# Battery_and_Charging.net
KiCad netlist of a schematic drawn in Altium Designer
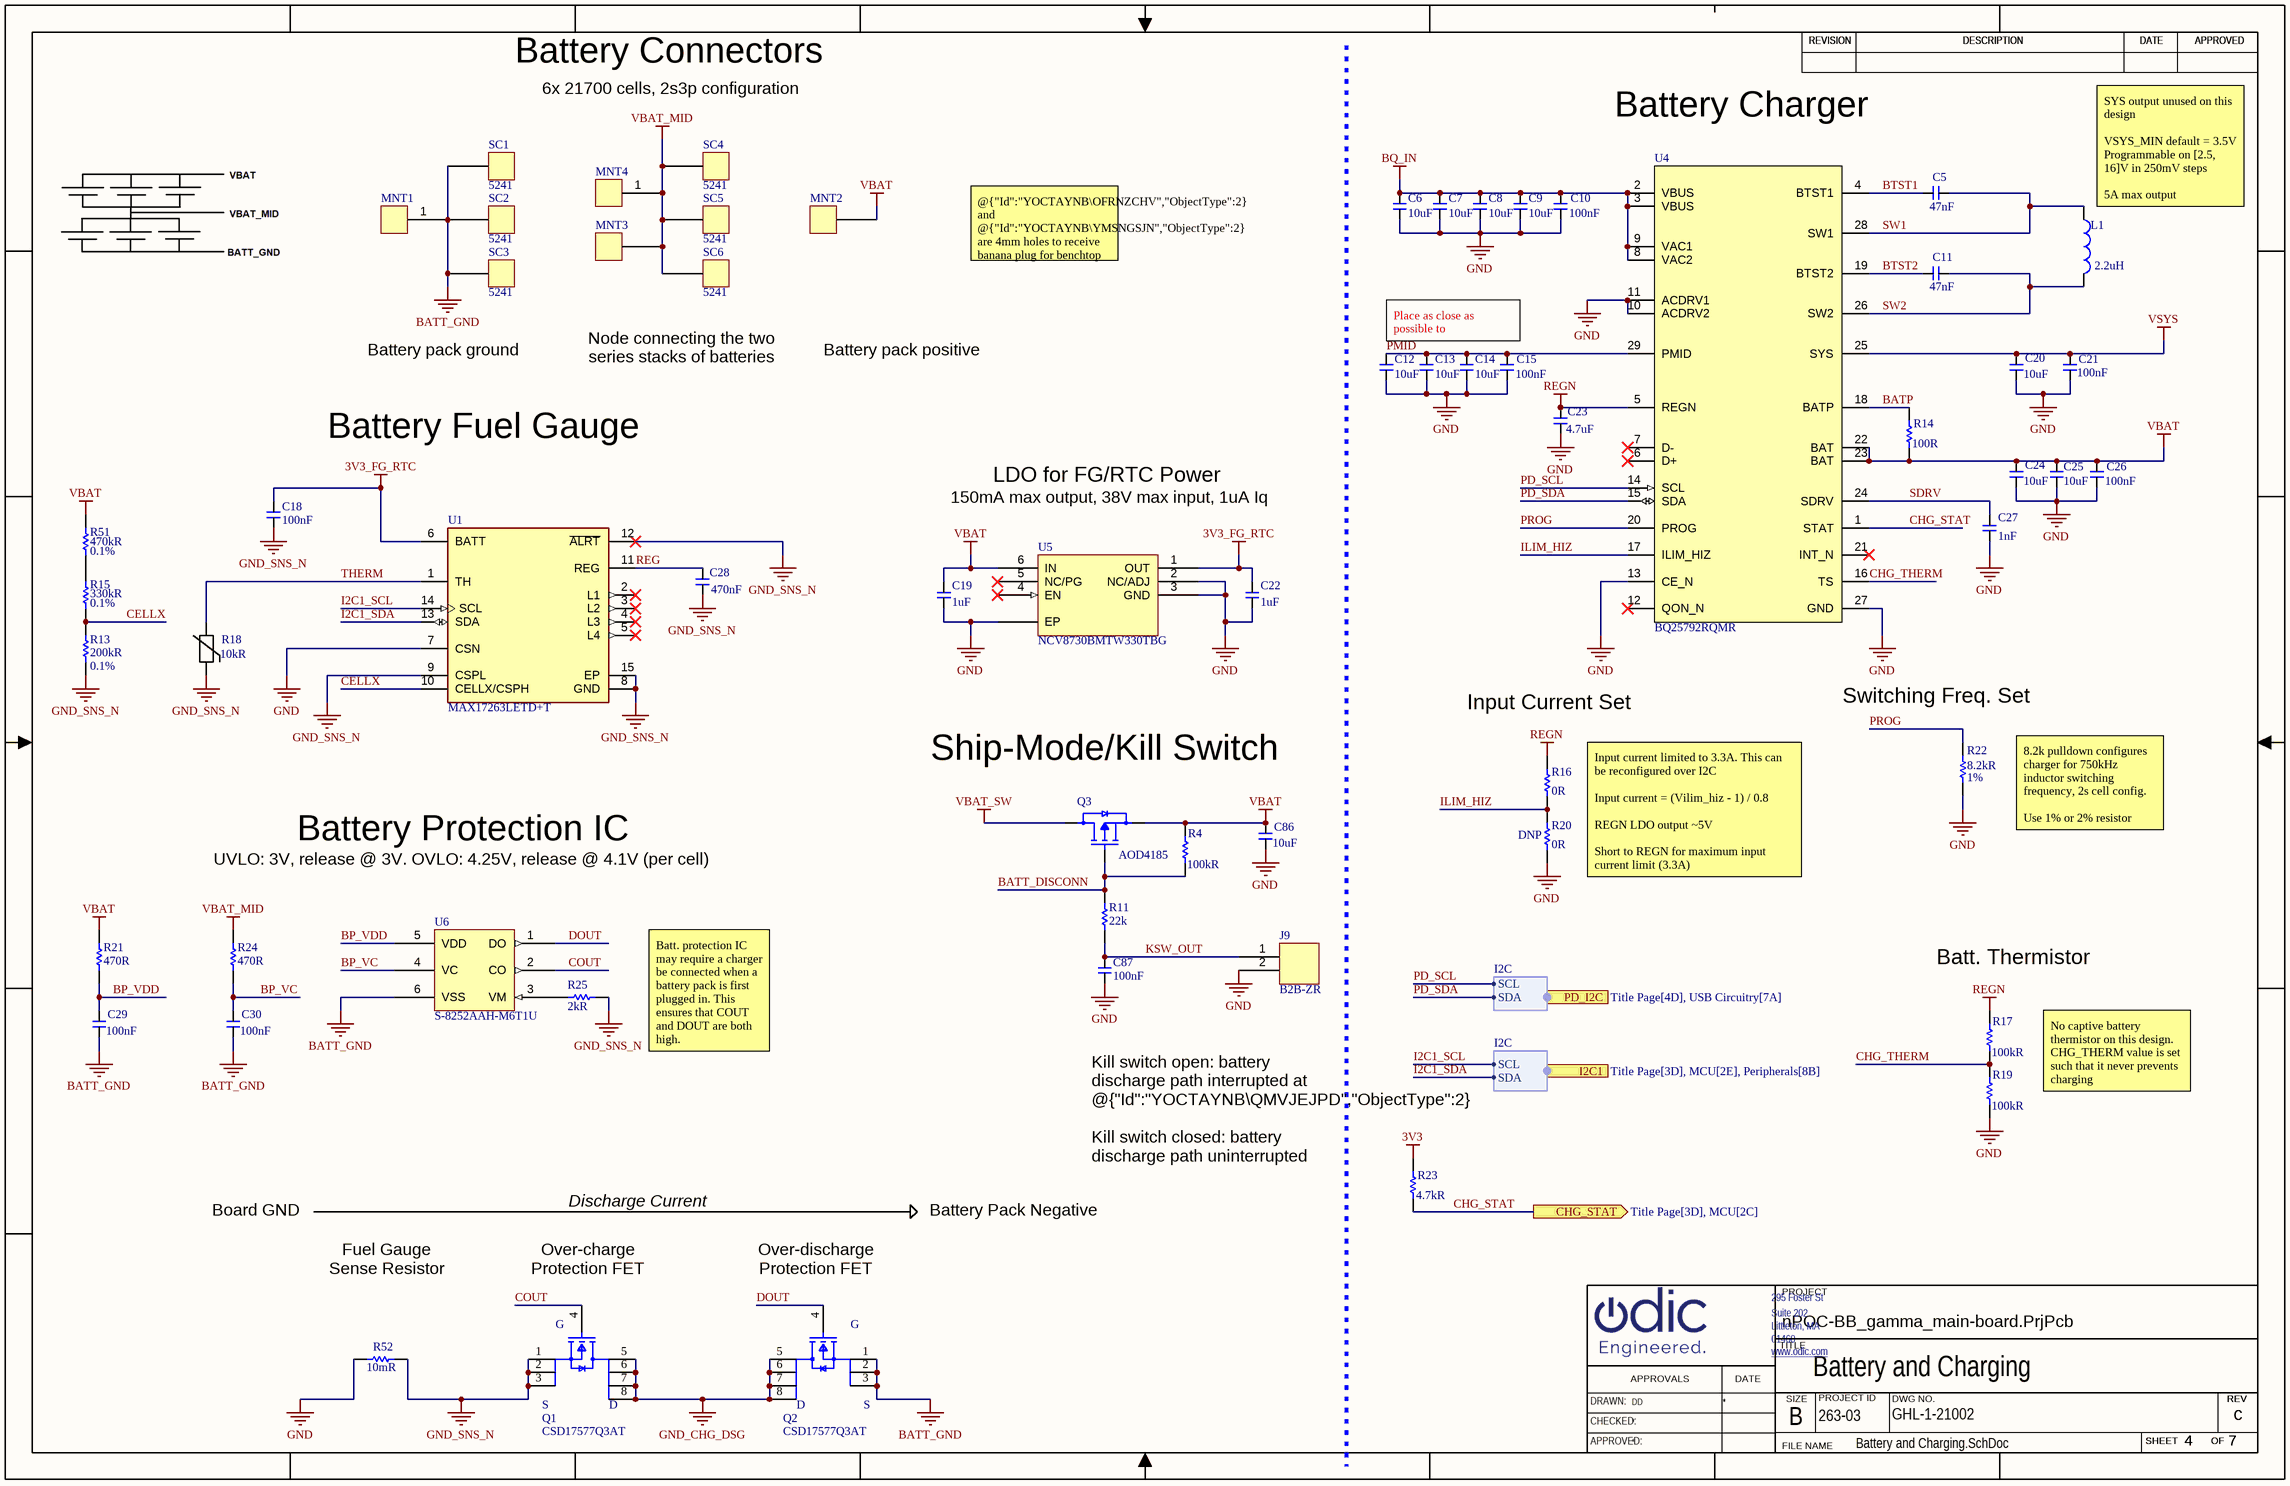
[diagram p0: Battery and Charging.SchDoc]

(export (version "E")
  (design (tool "Eeschema 10.0.6"))
  (components
    (comp (ref "C5")
      (value "C0402_47n_50V_10pct")
      (footprint "C0402")
      (description "CGA2B3X7R1H473K050BB")
      (fields (field (name "TOLERANCE") "10%") (field (name "CAPACITANCE") "47nF"))
      (libsource (lib "Odic Inc") (part "cAP"))
    )
    (comp (ref "C6")
      (value "C0603_10u_25V_10pct")
      (footprint "C0603")
      (description "GRM188R61E106KA73J")
      (fields (field (name "CAPACITANCE") "10uF") (field (name "TOLERANCE") "10%"))
      (libsource (lib "Odic Inc") (part "cAP"))
    )
    (comp (ref "C7")
      (value "C0603_10u_25V_10pct")
      (footprint "C0603")
      (description "GRM188R61E106KA73J")
      (fields (field (name "CAPACITANCE") "10uF") (field (name "TOLERANCE") "10%"))
      (libsource (lib "Odic Inc") (part "cAP"))
    )
    (comp (ref "C8")
      (value "C0603_10u_25V_10pct")
      (footprint "C0603")
      (description "GRM188R61E106KA73J")
      (fields (field (name "CAPACITANCE") "10uF") (field (name "TOLERANCE") "10%"))
      (libsource (lib "Odic Inc") (part "cAP"))
    )
    (comp (ref "C9")
      (value "C0603_10u_25V_10pct")
      (footprint "C0603")
      (description "GRM188R61E106KA73J")
      (fields (field (name "CAPACITANCE") "10uF") (field (name "TOLERANCE") "10%"))
      (libsource (lib "Odic Inc") (part "cAP"))
    )
    (comp (ref "C10")
      (value "C0402_0u1_25V_10pct")
      (footprint "C0402")
      (description "Cap Ceramic 0.1uF 25V X5R 10% Pad SMD 0402 Multi Layer Ceramic Capacitor (MLCC)")
      (fields
        (field (name "VOLTAGE") "25V")
        (field (name "TOLERANCE") "10%")
        (field (name "CAPACITANCE") "100nF")
      )
      (libsource (lib "Odic Inc") (part "cAP"))
    )
    (comp (ref "C11")
      (value "C0402_47n_50V_10pct")
      (footprint "C0402")
      (description "CGA2B3X7R1H473K050BB")
      (fields (field (name "TOLERANCE") "10%") (field (name "CAPACITANCE") "47nF"))
      (libsource (lib "Odic Inc") (part "cAP"))
    )
    (comp (ref "C12")
      (value "C0603_10u_25V_10pct")
      (footprint "C0603")
      (description "GRM188R61E106KA73J")
      (fields (field (name "CAPACITANCE") "10uF") (field (name "TOLERANCE") "10%"))
      (libsource (lib "Odic Inc") (part "cAP"))
    )
    (comp (ref "C13")
      (value "C0603_10u_25V_10pct")
      (footprint "C0603")
      (description "GRM188R61E106KA73J")
      (fields (field (name "CAPACITANCE") "10uF") (field (name "TOLERANCE") "10%"))
      (libsource (lib "Odic Inc") (part "cAP"))
    )
    (comp (ref "C14")
      (value "C0603_10u_25V_10pct")
      (footprint "C0603")
      (description "GRM188R61E106KA73J")
      (fields (field (name "CAPACITANCE") "10uF") (field (name "TOLERANCE") "10%"))
      (libsource (lib "Odic Inc") (part "cAP"))
    )
    (comp (ref "C15")
      (value "C0402_0u1_25V_10pct")
      (footprint "C0402")
      (description "Cap Ceramic 0.1uF 25V X5R 10% Pad SMD 0402 Multi Layer Ceramic Capacitor (MLCC)")
      (fields
        (field (name "VOLTAGE") "25V")
        (field (name "TOLERANCE") "10%")
        (field (name "CAPACITANCE") "100nF")
      )
      (libsource (lib "Odic Inc") (part "cAP"))
    )
    (comp (ref "C18")
      (value "C0402_100n_16V_10pct")
      (footprint "C0402")
      (description "0.1 µF ±10% 16V Ceramic Capacitor X7R 0402 (1005 Metric)")
      (fields
        (field (name "VOLTAGE") "16V")
        (field (name "TOLERANCE") "10%")
        (field (name "CAPACITANCE") "100nF")
      )
      (libsource (lib "Odic Inc") (part "cAP"))
    )
    (comp (ref "C19")
      (value "1uF")
      (footprint "C0402")
      (description "Ceramic capacitor SMD 0402 - 1000nF, 10V, +-10%, X5R")
      (fields (field (name "TOLERANCE") "10%") (field (name "Comment") "C0402_1u_10V_10pct"))
      (libsource (lib "Odic Inc") (part "cAP"))
    )
    (comp (ref "C20")
      (value "C0603_10u_25V_10pct")
      (footprint "C0603")
      (description "GRM188R61E106KA73J")
      (fields (field (name "CAPACITANCE") "10uF") (field (name "TOLERANCE") "10%"))
      (libsource (lib "Odic Inc") (part "cAP"))
    )
    (comp (ref "C21")
      (value "C0402_0u1_25V_10pct")
      (footprint "C0402")
      (description "Cap Ceramic 0.1uF 25V X5R 10% Pad SMD 0402 Multi Layer Ceramic Capacitor (MLCC)")
      (fields
        (field (name "VOLTAGE") "25V")
        (field (name "TOLERANCE") "10%")
        (field (name "CAPACITANCE") "100nF")
      )
      (libsource (lib "Odic Inc") (part "cAP"))
    )
    (comp (ref "C22")
      (value "1uF")
      (footprint "C0402")
      (description "Ceramic capacitor SMD 0402 - 1000nF, 10V, +-10%, X5R")
      (fields (field (name "TOLERANCE") "10%") (field (name "Comment") "C0402_1u_10V_10pct"))
      (libsource (lib "Odic Inc") (part "cAP"))
    )
    (comp (ref "C23")
      (value "C0402_4u7_10V_20pct")
      (footprint "C0402")
      (description "Cap Ceramic 4.7uF 10V X5R 20% SMD 0402 85°C Paper T/R")
      (fields (field (name "CAPACITANCE") "4.7uF") (field (name "TOLERANCE") "20%"))
      (libsource (lib "Odic Inc") (part "cAP"))
    )
    (comp (ref "C24")
      (value "C0603_10u_25V_10pct")
      (footprint "C0603")
      (description "GRM188R61E106KA73J")
      (fields (field (name "CAPACITANCE") "10uF") (field (name "TOLERANCE") "10%"))
      (libsource (lib "Odic Inc") (part "cAP"))
    )
    (comp (ref "C25")
      (value "C0603_10u_25V_10pct")
      (footprint "C0603")
      (description "GRM188R61E106KA73J")
      (fields (field (name "CAPACITANCE") "10uF") (field (name "TOLERANCE") "10%"))
      (libsource (lib "Odic Inc") (part "cAP"))
    )
    (comp (ref "C26")
      (value "C0402_0u1_25V_10pct")
      (footprint "C0402")
      (description "Cap Ceramic 0.1uF 25V X5R 10% Pad SMD 0402 Multi Layer Ceramic Capacitor (MLCC)")
      (fields
        (field (name "VOLTAGE") "25V")
        (field (name "TOLERANCE") "10%")
        (field (name "CAPACITANCE") "100nF")
      )
      (libsource (lib "Odic Inc") (part "cAP"))
    )
    (comp (ref "C27")
      (value "C0402_1n_50V_10pct")
      (footprint "C0402")
      (description "0402 1 nF 50V ±10 % Tolerance X7R Surface Mount Multilayer Ceramic Capacitor")
      (fields
        (field (name "TOLERANCE") "10%")
        (field (name "VOLTAGE") "50V")
        (field (name "CAPACITANCE") "1nF")
      )
      (libsource (lib "Odic Inc") (part "cAP"))
    )
    (comp (ref "C28")
      (value "C0402_470n_6V3_10pct")
      (footprint "C0402")
      (description "Ceramic capacitor SMD-0402 470nF 6.3V X5R +/-10%")
      (fields
        (field (name "CAPACITANCE") "470nF")
        (field (name "VOLTAGE") "6.3V")
        (field (name "TOLERANCE") "10%")
      )
      (libsource (lib "Odic Inc") (part "cAP"))
    )
    (comp (ref "C29")
      (value "100nF")
      (footprint "C0402")
      (description "Ceramic capacitor SMD 0402 100nF 16V X7R 10%")
      (fields (field (name "VOLTAGE") "16V") (field (name "TOLERANCE") "10%"))
      (libsource (lib "Odic Inc") (part "cAP"))
    )
    (comp (ref "C30")
      (value "100nF")
      (footprint "C0402")
      (description "Ceramic capacitor SMD 0402 100nF 16V X7R 10%")
      (fields (field (name "VOLTAGE") "16V") (field (name "TOLERANCE") "10%"))
      (libsource (lib "Odic Inc") (part "cAP"))
    )
    (comp (ref "C86")
      (value "C0603_10u_25V_10pct")
      (footprint "C0603")
      (description "GRM188R61E106KA73J")
      (fields (field (name "CAPACITANCE") "10uF") (field (name "TOLERANCE") "10%"))
      (libsource (lib "Odic Inc") (part "cAP"))
    )
    (comp (ref "C87")
      (value "C0402_100n_16V_10pct")
      (footprint "C0402")
      (description "0.1 µF ±10% 16V Ceramic Capacitor X7R 0402 (1005 Metric)")
      (fields
        (field (name "VOLTAGE") "16V")
        (field (name "TOLERANCE") "10%")
        (field (name "CAPACITANCE") "100nF")
      )
      (libsource (lib "Odic Inc") (part "cAP"))
    )
    (comp (ref "J9")
      (value "B2B-ZR")
      (footprint "jst-b2b-zr")
      (description "Board Connector, 2 Contact(s), 1 Row(s), Male, Straight, Solder Terminal")
      (libsource (lib "Odic Inc") (part "B2B-ZR-Symbol-1"))
    )
    (comp (ref "L1")
      (value "2.2uH")
      (footprint "ind2_5p4x5p2mm")
      (description "FIXED IND 2.2UH 5.8A 29 MOHM")
      (fields (field (name "TOLERANCE") "20%") (field (name "Comment") "0530CDMCCDS-2R2MC"))
      (libsource (lib "Odic Inc") (part "IND"))
    )
    (comp (ref "MNT1")
      (value "Banana Plug Hole")
      (footprint "conn_wire-1_4mm")
      (description "4mm hole to accept banana plug")
      (libsource (lib "Odic Inc") (part "Banana Plug Hole-Symbol-1"))
    )
    (comp (ref "MNT2")
      (value "SOLDER HOLE 10AWG")
      (footprint "conn_wire-1")
      (description "Hole for 10AWG solder connection")
      (libsource (lib "Odic Inc") (part "SOLDER HOLE-Symbol-1"))
    )
    (comp (ref "MNT3")
      (value "SOLDER HOLE 10AWG")
      (footprint "conn_wire-1")
      (description "Hole for 10AWG solder connection")
      (libsource (lib "Odic Inc") (part "SOLDER HOLE-Symbol-1"))
    )
    (comp (ref "MNT4")
      (value "Banana Plug Hole")
      (footprint "conn_wire-1_4mm")
      (description "4mm hole to accept banana plug")
      (libsource (lib "Odic Inc") (part "Banana Plug Hole-Symbol-1"))
    )
    (comp (ref "Q1")
      (value "CSD17577Q3AT")
      (footprint "dfn8_3p1x3p25_p65mm")
      (description "30-V, N channel NexFET™ power MOSFET, single SON 3 mm x 3 mm, 6.4 mOhm 8-VSONP -55 to 150")
      (libsource (lib "Odic Inc") (part "CSD17577Q3AT-symbol"))
    )
    (comp (ref "Q2")
      (value "CSD17577Q3AT")
      (footprint "dfn8_3p1x3p25_p65mm")
      (description "30-V, N channel NexFET™ power MOSFET, single SON 3 mm x 3 mm, 6.4 mOhm 8-VSONP -55 to 150")
      (libsource (lib "Odic Inc") (part "CSD17577Q3AT-symbol"))
    )
    (comp (ref "Q3")
      (value "AOD4185")
      (footprint "TO-252")
      (description "Trans MOSFET P-CH 40V 40A 3-Pin(2+Tab) DPAK")
      (libsource (lib "Odic Inc") (part "FQD2P40TM"))
    )
    (comp (ref "R4")
      (value "R0402_100k_1pct")
      (footprint "R0402")
      (description "Res General Purpose Thick Film 0402 100K Ohm 1% 1/16W ±100ppm/°C Molded SMD Paper T/R")
      (fields (field (name "RESISTANCE") "100kR") (field (name "TOLERANCE") "1%"))
      (libsource (lib "Odic Inc") (part "RES"))
    )
    (comp (ref "R11")
      (value "22k")
      (footprint "R0402")
      (description "Res Thick Film 0402 22K Ohm 1% 0.063W(1/16W) ±100ppm/C Pad SMD T/R")
      (fields (field (name "TOLERANCE") "1%"))
      (libsource (lib "Odic Inc") (part "RES"))
    )
    (comp (ref "R13")
      (value "200kR")
      (footprint "R0402")
      (description "SMD Chip Resistor, 200 kOhm, ± 0.1%, 63 mW, 0402 [1005 Metric], Thin Film, Precision")
      (fields (field (name "TOLERANCE") "0.1%") (field (name "Comment") "R0402_200k_0.1pct"))
      (libsource (lib "Odic Inc") (part "RES"))
    )
    (comp (ref "R14")
      (value "100R")
      (footprint "R0402")
      (description "Res General Purpose Thick Film 0402 100 Ohm 1% 1/16W ±200ppm/°C Molded SMD Paper T/R")
      (fields (field (name "TOLERANCE") "1%") (field (name "Comment") "R0402_100R_1pct"))
      (libsource (lib "Odic Inc") (part "RES"))
    )
    (comp (ref "R15")
      (value "330kR")
      (footprint "R0402")
      (description "Res, 330K, 0.1W, 0402, Thin Film Rohs Compliant: Yes")
      (fields (field (name "TOLERANCE") "0.1%") (field (name "Comment") "R0402_330k_0p1pct"))
      (libsource (lib "Odic Inc") (part "RES"))
    )
    (comp (ref "R16")
      (value "R0402_0R")
      (footprint "R0402")
      (description "RES 0 OHM JUMPER 1/16W 0402")
      (fields (field (name "RESISTANCE") "0R"))
      (libsource (lib "Odic Inc") (part "RES"))
    )
    (comp (ref "R17")
      (value "R0402_100k_1pct")
      (footprint "R0402")
      (description "Res General Purpose Thick Film 0402 100K Ohm 1% 1/16W ±100ppm/°C Molded SMD Paper T/R")
      (fields (field (name "RESISTANCE") "100kR") (field (name "TOLERANCE") "1%"))
      (libsource (lib "Odic Inc") (part "RES"))
    )
    (comp (ref "R18")
      (value "10kR")
      (footprint "R0603")
      (description "NTC Thermistor 10k 0603 (1608 Metric)")
      (fields (field (name "Comment") "NCU18XH103F6SRB"))
      (libsource (lib "Odic Inc") (part "THERM"))
    )
    (comp (ref "R19")
      (value "R0402_100k_1pct")
      (footprint "R0402")
      (description "Res General Purpose Thick Film 0402 100K Ohm 1% 1/16W ±100ppm/°C Molded SMD Paper T/R")
      (fields (field (name "RESISTANCE") "100kR") (field (name "TOLERANCE") "1%"))
      (libsource (lib "Odic Inc") (part "RES"))
    )
    (comp (ref "R20")
      (value "R0402_0R")
      (footprint "R0402")
      (description "RES 0 OHM JUMPER 1/16W 0402")
      (fields (field (name "INSTALL") "DNP") (field (name "RESISTANCE") "0R"))
      (libsource (lib "Odic Inc") (part "RES"))
    )
    (comp (ref "R21")
      (value "R0402_470R_1pct")
      (footprint "R0402")
      (description "Res Thick Film 0402 470 Ohm 1% 0.063W(1/16W) ±100ppm/C Pad SMD T/R")
      (fields (field (name "TOLERANCE") "1%") (field (name "RESISTANCE") "470R"))
      (libsource (lib "Odic Inc") (part "RES"))
    )
    (comp (ref "R22")
      (value "8.2kR")
      (footprint "R0402")
      (description "SMD Chip Resistor, 8.2 kOhm, ± 1%, 62.5 mW, 0402 [1005 Metric], Thick Film, General Purpose")
      (fields
        (field (name "RESISTANCE TOLERANCE") "1%")
        (field (name "TOLERANCE") "1%")
        (field (name "Comment") "R0402_8k2_1pct")
      )
      (libsource (lib "Odic Inc") (part "RES"))
    )
    (comp (ref "R23")
      (value "R0402_4k7_1pct")
      (footprint "R0402")
      (description "RES 4.7K OHM 1% 1/16W 0402")
      (fields (field (name "TOLERANCE") "1%") (field (name "RESISTANCE") "4.7kR"))
      (libsource (lib "Odic Inc") (part "RES"))
    )
    (comp (ref "R24")
      (value "R0402_470R_1pct")
      (footprint "R0402")
      (description "Res Thick Film 0402 470 Ohm 1% 0.063W(1/16W) ±100ppm/C Pad SMD T/R")
      (fields (field (name "TOLERANCE") "1%") (field (name "RESISTANCE") "470R"))
      (libsource (lib "Odic Inc") (part "RES"))
    )
    (comp (ref "R25")
      (value "R0402_2k_1pct")
      (footprint "R0402")
      (description "Res General Purpose Thick Film 0402 2K Ohm 1% 1/16W ±100ppm/°C Molded SMD Paper T/R")
      (fields (field (name "TOLERANCE") "1%") (field (name "RESISTANCE") "2kR"))
      (libsource (lib "Odic Inc") (part "RES"))
    )
    (comp (ref "R51")
      (value "470kR")
      (footprint "R0402")
      (description "470 kOhms 0.1% 0.063W, 1/16W Chip Resistor 0402 (1005 Metric) Anti-Sulfur, Autom")
      (fields (field (name "TOLERANCE") "0.1%") (field (name "Comment") "R0402_470k_0p1pct"))
      (libsource (lib "Odic Inc") (part "RES"))
    )
    (comp (ref "R52")
      (value "10mR")
      (footprint "R2010_alt")
      (description "Res Current Sense Metal Strip 2010 0.01 Ohm 1% 2W ±75ppm/°C Molded Emboss T/R")
      (fields (field (name "Comment") "R2010_10m_1pct"))
      (libsource (lib "Odic Inc") (part "RES"))
    )
    (comp (ref "SC1")
      (value "5241")
      (footprint "bat_keystone-5241")
      (description "Cylindrical Battery Contacts, Clips, Holders & Springs C Cell Negative Battery Contact")
      (libsource (lib "Odic Inc") (part "5241-Symbol-1"))
    )
    (comp (ref "SC2")
      (value "5241")
      (footprint "bat_keystone-5241")
      (description "Cylindrical Battery Contacts, Clips, Holders & Springs C Cell Negative Battery Contact")
      (libsource (lib "Odic Inc") (part "5241-Symbol-1"))
    )
    (comp (ref "SC3")
      (value "5241")
      (footprint "bat_keystone-5241")
      (description "Cylindrical Battery Contacts, Clips, Holders & Springs C Cell Negative Battery Contact")
      (libsource (lib "Odic Inc") (part "5241-Symbol-1"))
    )
    (comp (ref "SC4")
      (value "5241")
      (footprint "bat_keystone-5241")
      (description "Cylindrical Battery Contacts, Clips, Holders & Springs C Cell Negative Battery Contact")
      (libsource (lib "Odic Inc") (part "5241-Symbol-1"))
    )
    (comp (ref "SC5")
      (value "5241")
      (footprint "bat_keystone-5241")
      (description "Cylindrical Battery Contacts, Clips, Holders & Springs C Cell Negative Battery Contact")
      (libsource (lib "Odic Inc") (part "5241-Symbol-1"))
    )
    (comp (ref "SC6")
      (value "5241")
      (footprint "bat_keystone-5241")
      (description "Cylindrical Battery Contacts, Clips, Holders & Springs C Cell Negative Battery Contact")
      (libsource (lib "Odic Inc") (part "5241-Symbol-1"))
    )
    (comp (ref "U1")
      (value "MAX17263LETD+T")
      (footprint "dfn14_3x3_p4mm")
      (description "MAX17263 Series 4.9 V Single/Multi-Cell Ultra-Low Power Fuel-Gauge IC-TDFN-14EP")
      (libsource (lib "Odic Inc") (part "9e6c63fd24431d9ce7a831344c264e3"))
    )
    (comp (ref "U4")
      (value "BQ25792RQMR")
      (footprint "qfn29_4x4_p4mm-RQM0029A")
      (description "I2C Controlled, 1-4 Cell, 5-A Buck-Boost Battery Charger with Dual-Input")
      (libsource (lib "Odic Inc") (part "PQ25792RQMR"))
    )
    (comp (ref "U5")
      (value "NCV8730BMTW330TBG")
      (footprint "dfn7_2x2_p65mm_onsemi")
      (description "LDO Regulator, 150 mA, 38 V, 1 µA IQ, with PG 3.3V WDFNW6")
      (libsource (lib "Odic Inc") (part "NCV8730BMTW330TBG-Symbol-1"))
    )
    (comp (ref "U6")
      (value "S-8252AAH-M6T1U")
      (footprint "SOT23-6PIN")
      (description "Battery Protection Li-Ion/Li-Pol 6-Pin SOT-23 T/R")
      (libsource (lib "Odic Inc") (part "S-8252-series-symbol"))
    )
  )
  (nets
    (net (code "2") (name "/BATP") (class "Default")
      (node (ref "R14") (pin "2") (pinfunction "2_2") (pintype "passive"))
      (node (ref "U4") (pin "18") (pinfunction "BATP_18") (pintype "passive"))
    )
    (net (code "3") (name "/BATT_DISCONN") (class "Default")
      (node (ref "Q3") (pin "1") (pinfunction "G_1") (pintype "passive"))
      (node (ref "R11") (pin "2") (pinfunction "2_2") (pintype "passive"))
      (node (ref "R4") (pin "1") (pinfunction "1_1") (pintype "passive"))
    )
    (net (code "4") (name "/BP_VC") (class "Default")
      (node (ref "C30") (pin "2") (pinfunction "2_2") (pintype "passive"))
      (node (ref "R24") (pin "2") (pinfunction "2_2") (pintype "passive"))
      (node (ref "U6") (pin "4") (pinfunction "VC_4") (pintype "passive"))
    )
    (net (code "5") (name "/BP_VDD") (class "Default")
      (node (ref "C29") (pin "2") (pinfunction "2_2") (pintype "passive"))
      (node (ref "R21") (pin "2") (pinfunction "2_2") (pintype "passive"))
      (node (ref "U6") (pin "5") (pinfunction "VDD_5") (pintype "passive"))
    )
    (net (code "6") (name "/BTST1") (class "Default")
      (node (ref "C5") (pin "2") (pinfunction "2_2") (pintype "passive"))
      (node (ref "U4") (pin "4") (pinfunction "BTST1_4") (pintype "passive"))
    )
    (net (code "7") (name "/BTST2") (class "Default")
      (node (ref "C11") (pin "2") (pinfunction "2_2") (pintype "passive"))
      (node (ref "U4") (pin "19") (pinfunction "BTST2_19") (pintype "passive"))
    )
    (net (code "8") (name "/CELLX") (class "Default")
      (node (ref "R13") (pin "1") (pinfunction "1_1") (pintype "passive"))
      (node (ref "R15") (pin "1") (pinfunction "1_1") (pintype "passive"))
      (node (ref "U1") (pin "10") (pinfunction "CELLX/CSPH_10") (pintype "passive"))
    )
    (net (code "9") (name "/CHG_STAT") (class "Default")
      (node (ref "R23") (pin "1") (pinfunction "1_1") (pintype "passive"))
      (node (ref "U4") (pin "1") (pinfunction "STAT_1") (pintype "passive"))
    )
    (net (code "10") (name "/CHG_THERM") (class "Default")
      (node (ref "R17") (pin "1") (pinfunction "1_1") (pintype "passive"))
      (node (ref "R19") (pin "2") (pinfunction "2_2") (pintype "passive"))
      (node (ref "U4") (pin "16") (pinfunction "TS_16") (pintype "passive"))
    )
    (net (code "11") (name "/COUT") (class "Default")
      (node (ref "Q1") (pin "4") (pinfunction "G_4") (pintype "passive"))
      (node (ref "U6") (pin "2") (pinfunction "CO_2") (pintype "output"))
    )
    (net (code "12") (name "/DOUT") (class "Default")
      (node (ref "Q2") (pin "4") (pinfunction "G_4") (pintype "passive"))
      (node (ref "U6") (pin "1") (pinfunction "DO_1") (pintype "output"))
    )
    (net (code "13") (name "/I2C1_SCL") (class "Default")
      (node (ref "U1") (pin "14") (pinfunction "SCL_14") (pintype "input"))
    )
    (net (code "14") (name "/I2C1_SDA") (class "Default")
      (node (ref "U1") (pin "13") (pinfunction "SDA_13") (pintype "bidirectional"))
    )
    (net (code "15") (name "/ILIM_HIZ") (class "Default")
      (node (ref "R16") (pin "1") (pinfunction "1_1") (pintype "passive"))
      (node (ref "R20") (pin "2") (pinfunction "2_2") (pintype "passive"))
      (node (ref "U4") (pin "17") (pinfunction "ILIM_HIZ_17") (pintype "passive"))
    )
    (net (code "16") (name "/KSW_OUT") (class "Default")
      (node (ref "C87") (pin "1") (pinfunction "1_1") (pintype "passive"))
      (node (ref "J9") (pin "1") (pinfunction "1_1") (pintype "passive"))
      (node (ref "R11") (pin "1") (pinfunction "1_1") (pintype "passive"))
    )
    (net (code "17") (name "/PD_SCL") (class "Default")
      (node (ref "U4") (pin "14") (pinfunction "SCL_14") (pintype "input"))
    )
    (net (code "18") (name "/PD_SDA") (class "Default")
      (node (ref "U4") (pin "15") (pinfunction "SDA_15") (pintype "bidirectional"))
    )
    (net (code "19") (name "/PMID") (class "Default")
      (node (ref "C12") (pin "2") (pinfunction "2_2") (pintype "passive"))
      (node (ref "C13") (pin "2") (pinfunction "2_2") (pintype "passive"))
      (node (ref "C14") (pin "2") (pinfunction "2_2") (pintype "passive"))
      (node (ref "C15") (pin "2") (pinfunction "2_2") (pintype "passive"))
      (node (ref "U4") (pin "29") (pinfunction "PMID_29") (pintype "passive"))
    )
    (net (code "20") (name "/PROG") (class "Default")
      (node (ref "R22") (pin "2") (pinfunction "2_2") (pintype "passive"))
      (node (ref "U4") (pin "20") (pinfunction "PROG_20") (pintype "passive"))
    )
    (net (code "21") (name "/REG") (class "Default")
      (node (ref "C28") (pin "2") (pinfunction "2_2") (pintype "passive"))
      (node (ref "U1") (pin "11") (pinfunction "REG_11") (pintype "power_in"))
    )
    (net (code "22") (name "/SDRV") (class "Default")
      (node (ref "C27") (pin "2") (pinfunction "2_2") (pintype "passive"))
      (node (ref "U4") (pin "24") (pinfunction "SDRV_24") (pintype "passive"))
    )
    (net (code "23") (name "/SW1") (class "Default")
      (node (ref "C5") (pin "1") (pinfunction "1_1") (pintype "passive"))
      (node (ref "L1") (pin "1") (pinfunction "1_1") (pintype "passive"))
      (node (ref "U4") (pin "28") (pinfunction "SW1_28") (pintype "passive"))
    )
    (net (code "24") (name "/SW2") (class "Default")
      (node (ref "C11") (pin "1") (pinfunction "1_1") (pintype "passive"))
      (node (ref "L1") (pin "2") (pinfunction "2_2") (pintype "passive"))
      (node (ref "U4") (pin "26") (pinfunction "SW2_26") (pintype "passive"))
    )
    (net (code "25") (name "/THERM") (class "Default")
      (node (ref "R18") (pin "2") (pinfunction "2_2") (pintype "passive"))
      (node (ref "U1") (pin "1") (pinfunction "TH_1") (pintype "passive"))
    )
    (net (code "27") (name "3V3") (class "Default")
      (node (ref "R23") (pin "2") (pinfunction "2_2") (pintype "passive"))
    )
    (net (code "28") (name "3V3_FG_RTC") (class "Default")
      (node (ref "C18") (pin "1") (pinfunction "1_1") (pintype "passive"))
      (node (ref "C22") (pin "2") (pinfunction "2_2") (pintype "passive"))
      (node (ref "U1") (pin "6") (pinfunction "BATT_6") (pintype "power_in"))
      (node (ref "U5") (pin "1") (pinfunction "OUT_1") (pintype "power_in"))
    )
    (net (code "29") (name "BATT_GND") (class "Default")
      (node (ref "C29") (pin "1") (pinfunction "1_1") (pintype "passive"))
      (node (ref "C30") (pin "1") (pinfunction "1_1") (pintype "passive"))
      (node (ref "MNT1") (pin "1") (pinfunction "1_1") (pintype "passive"))
      (node (ref "Q2") (pin "1") (pinfunction "S_1") (pintype "passive"))
      (node (ref "Q2") (pin "2") (pinfunction "S_2") (pintype "passive"))
      (node (ref "Q2") (pin "3") (pinfunction "S_3") (pintype "passive"))
      (node (ref "SC1") (pin "1") (pinfunction "1_1") (pintype "passive"))
      (node (ref "SC2") (pin "1") (pinfunction "1_1") (pintype "passive"))
      (node (ref "SC3") (pin "1") (pinfunction "1_1") (pintype "passive"))
      (node (ref "U6") (pin "6") (pinfunction "VSS_6") (pintype "passive"))
    )
    (net (code "30") (name "BQ_IN") (class "Default")
      (node (ref "C10") (pin "2") (pinfunction "2_2") (pintype "passive"))
      (node (ref "C6") (pin "2") (pinfunction "2_2") (pintype "passive"))
      (node (ref "C7") (pin "2") (pinfunction "2_2") (pintype "passive"))
      (node (ref "C8") (pin "2") (pinfunction "2_2") (pintype "passive"))
      (node (ref "C9") (pin "2") (pinfunction "2_2") (pintype "passive"))
      (node (ref "U4") (pin "2") (pinfunction "VBUS_2") (pintype "power_in"))
      (node (ref "U4") (pin "3") (pinfunction "VBUS_3") (pintype "power_in"))
      (node (ref "U4") (pin "8") (pinfunction "VAC2_8") (pintype "power_in"))
      (node (ref "U4") (pin "9") (pinfunction "VAC1_9") (pintype "power_in"))
    )
    (net (code "31") (name "GND") (class "Default")
      (node (ref "C10") (pin "1") (pinfunction "1_1") (pintype "passive"))
      (node (ref "C12") (pin "1") (pinfunction "1_1") (pintype "passive"))
      (node (ref "C13") (pin "1") (pinfunction "1_1") (pintype "passive"))
      (node (ref "C14") (pin "1") (pinfunction "1_1") (pintype "passive"))
      (node (ref "C15") (pin "1") (pinfunction "1_1") (pintype "passive"))
      (node (ref "C19") (pin "1") (pinfunction "1_1") (pintype "passive"))
      (node (ref "C20") (pin "1") (pinfunction "1_1") (pintype "passive"))
      (node (ref "C21") (pin "1") (pinfunction "1_1") (pintype "passive"))
      (node (ref "C22") (pin "1") (pinfunction "1_1") (pintype "passive"))
      (node (ref "C23") (pin "1") (pinfunction "1_1") (pintype "passive"))
      (node (ref "C24") (pin "1") (pinfunction "1_1") (pintype "passive"))
      (node (ref "C25") (pin "1") (pinfunction "1_1") (pintype "passive"))
      (node (ref "C26") (pin "1") (pinfunction "1_1") (pintype "passive"))
      (node (ref "C27") (pin "1") (pinfunction "1_1") (pintype "passive"))
      (node (ref "C6") (pin "1") (pinfunction "1_1") (pintype "passive"))
      (node (ref "C7") (pin "1") (pinfunction "1_1") (pintype "passive"))
      (node (ref "C8") (pin "1") (pinfunction "1_1") (pintype "passive"))
      (node (ref "C86") (pin "1") (pinfunction "1_1") (pintype "passive"))
      (node (ref "C87") (pin "2") (pinfunction "2_2") (pintype "passive"))
      (node (ref "C9") (pin "1") (pinfunction "1_1") (pintype "passive"))
      (node (ref "J9") (pin "2") (pinfunction "2_2") (pintype "passive"))
      (node (ref "R19") (pin "1") (pinfunction "1_1") (pintype "passive"))
      (node (ref "R20") (pin "1") (pinfunction "1_1") (pintype "passive"))
      (node (ref "R22") (pin "1") (pinfunction "1_1") (pintype "passive"))
      (node (ref "R52") (pin "1") (pinfunction "1_1") (pintype "passive"))
      (node (ref "U1") (pin "7") (pinfunction "CSN_7") (pintype "passive"))
      (node (ref "U4") (pin "10") (pinfunction "ACDRV2_10") (pintype "power_in"))
      (node (ref "U4") (pin "11") (pinfunction "ACDRV1_11") (pintype "power_in"))
      (node (ref "U4") (pin "13") (pinfunction "CE_N_13") (pintype "passive"))
      (node (ref "U4") (pin "27") (pinfunction "GND_27") (pintype "power_in"))
      (node (ref "U5") (pin "2") (pinfunction "NC/ADJ_2") (pintype "passive"))
      (node (ref "U5") (pin "3") (pinfunction "GND_3") (pintype "passive"))
      (node (ref "U5") (pin "EP") (pinfunction "EP_EP") (pintype "passive"))
    )
    (net (code "32") (name "GND_CHG_DSG") (class "Default")
      (node (ref "Q1") (pin "5") (pinfunction "D_5") (pintype "passive"))
      (node (ref "Q1") (pin "6") (pinfunction "D_6") (pintype "passive"))
      (node (ref "Q1") (pin "7") (pinfunction "D_7") (pintype "passive"))
      (node (ref "Q1") (pin "8") (pinfunction "D_8") (pintype "passive"))
      (node (ref "Q2") (pin "5") (pinfunction "D_5") (pintype "passive"))
      (node (ref "Q2") (pin "6") (pinfunction "D_6") (pintype "passive"))
      (node (ref "Q2") (pin "7") (pinfunction "D_7") (pintype "passive"))
      (node (ref "Q2") (pin "8") (pinfunction "D_8") (pintype "passive"))
    )
    (net (code "33") (name "GND_SNS_N") (class "Default")
      (node (ref "C18") (pin "2") (pinfunction "2_2") (pintype "passive"))
      (node (ref "C28") (pin "1") (pinfunction "1_1") (pintype "passive"))
      (node (ref "Q1") (pin "1") (pinfunction "S_1") (pintype "passive"))
      (node (ref "Q1") (pin "2") (pinfunction "S_2") (pintype "passive"))
      (node (ref "Q1") (pin "3") (pinfunction "S_3") (pintype "passive"))
      (node (ref "R13") (pin "2") (pinfunction "2_2") (pintype "passive"))
      (node (ref "R18") (pin "1") (pinfunction "1_1") (pintype "passive"))
      (node (ref "R25") (pin "2") (pinfunction "2_2") (pintype "passive"))
      (node (ref "R52") (pin "2") (pinfunction "2_2") (pintype "passive"))
      (node (ref "U1") (pin "12") (pinfunction "~{ALRT}_12") (pintype "open_collector"))
      (node (ref "U1") (pin "15") (pinfunction "EP_15") (pintype "power_in"))
      (node (ref "U1") (pin "8") (pinfunction "GND_8") (pintype "power_in"))
      (node (ref "U1") (pin "9") (pinfunction "CSPL_9") (pintype "passive"))
    )
    (net (code "34") (name "Net-(R15-Pad2)") (class "Default")
      (node (ref "R15") (pin "2") (pinfunction "2_2") (pintype "passive"))
      (node (ref "R51") (pin "1") (pinfunction "1_1") (pintype "passive"))
    )
    (net (code "35") (name "Net-(U6-VM)") (class "Default")
      (node (ref "R25") (pin "1") (pinfunction "1_1") (pintype "passive"))
      (node (ref "U6") (pin "3") (pinfunction "VM_3") (pintype "input"))
    )
    (net (code "36") (name "REGN") (class "Default")
      (node (ref "C23") (pin "2") (pinfunction "2_2") (pintype "passive"))
      (node (ref "R16") (pin "2") (pinfunction "2_2") (pintype "passive"))
      (node (ref "R17") (pin "2") (pinfunction "2_2") (pintype "passive"))
      (node (ref "U4") (pin "5") (pinfunction "REGN_5") (pintype "passive"))
    )
    (net (code "37") (name "VBAT") (class "Default")
      (node (ref "C19") (pin "2") (pinfunction "2_2") (pintype "passive"))
      (node (ref "C24") (pin "2") (pinfunction "2_2") (pintype "passive"))
      (node (ref "C25") (pin "2") (pinfunction "2_2") (pintype "passive"))
      (node (ref "C26") (pin "2") (pinfunction "2_2") (pintype "passive"))
      (node (ref "C86") (pin "2") (pinfunction "2_2") (pintype "passive"))
      (node (ref "MNT2") (pin "1") (pinfunction "1_1") (pintype "passive"))
      (node (ref "Q3") (pin "2") (pinfunction "S_2") (pintype "passive"))
      (node (ref "R14") (pin "1") (pinfunction "1_1") (pintype "passive"))
      (node (ref "R21") (pin "1") (pinfunction "1_1") (pintype "passive"))
      (node (ref "R4") (pin "2") (pinfunction "2_2") (pintype "passive"))
      (node (ref "R51") (pin "2") (pinfunction "2_2") (pintype "passive"))
      (node (ref "U4") (pin "22") (pinfunction "BAT_22") (pintype "passive"))
      (node (ref "U4") (pin "23") (pinfunction "BAT_23") (pintype "passive"))
      (node (ref "U5") (pin "6") (pinfunction "IN_6") (pintype "power_in"))
    )
    (net (code "38") (name "VBAT_MID") (class "Default")
      (node (ref "MNT3") (pin "1") (pinfunction "1_1") (pintype "passive"))
      (node (ref "MNT4") (pin "1") (pinfunction "1_1") (pintype "passive"))
      (node (ref "R24") (pin "1") (pinfunction "1_1") (pintype "passive"))
      (node (ref "SC4") (pin "1") (pinfunction "1_1") (pintype "passive"))
      (node (ref "SC5") (pin "1") (pinfunction "1_1") (pintype "passive"))
      (node (ref "SC6") (pin "1") (pinfunction "1_1") (pintype "passive"))
    )
    (net (code "39") (name "VBAT_SW") (class "Default")
      (node (ref "Q3") (pin "3") (pinfunction "D_3") (pintype "passive"))
    )
    (net (code "40") (name "VSYS") (class "Default")
      (node (ref "C20") (pin "2") (pinfunction "2_2") (pintype "passive"))
      (node (ref "C21") (pin "2") (pinfunction "2_2") (pintype "passive"))
      (node (ref "U4") (pin "25") (pinfunction "SYS_25") (pintype "passive"))
    )
    (net (code "41") (name "unconnected-(U1-L1-Pad2)") (class "Default")
      (node (ref "U1") (pin "2") (pinfunction "L1_2") (pintype "output+no_connect"))
    )
    (net (code "42") (name "unconnected-(U1-L2-Pad3)") (class "Default")
      (node (ref "U1") (pin "3") (pinfunction "L2_3") (pintype "output+no_connect"))
    )
    (net (code "43") (name "unconnected-(U1-L3-Pad4)") (class "Default")
      (node (ref "U1") (pin "4") (pinfunction "L3_4") (pintype "output+no_connect"))
    )
    (net (code "44") (name "unconnected-(U1-L4-Pad5)") (class "Default")
      (node (ref "U1") (pin "5") (pinfunction "L4_5") (pintype "output+no_connect"))
    )
    (net (code "45") (name "unconnected-(U4-D+-Pad6)") (class "Default")
      (node (ref "U4") (pin "6") (pinfunction "D+_6") (pintype "passive+no_connect"))
    )
    (net (code "46") (name "unconnected-(U4-D--Pad7)") (class "Default")
      (node (ref "U4") (pin "7") (pinfunction "D-_7") (pintype "passive+no_connect"))
    )
    (net (code "47") (name "unconnected-(U4-INT_N-Pad21)") (class "Default")
      (node (ref "U4") (pin "21") (pinfunction "INT_N_21") (pintype "passive+no_connect"))
    )
    (net (code "48") (name "unconnected-(U4-QON_N-Pad12)") (class "Default")
      (node (ref "U4") (pin "12") (pinfunction "QON_N_12") (pintype "passive+no_connect"))
    )
    (net (code "49") (name "unconnected-(U5-EN-Pad4)") (class "Default")
      (node (ref "U5") (pin "4") (pinfunction "EN_4") (pintype "input+no_connect"))
    )
    (net (code "50") (name "unconnected-(U5-NC{slash}PG-Pad5)") (class "Default")
      (node (ref "U5") (pin "5") (pinfunction "NC/PG_5") (pintype "passive+no_connect"))
    )
  )
)
